# FC_v2_0_Schematic.net
KiCad netlist of a schematic drawn in Altium Designer
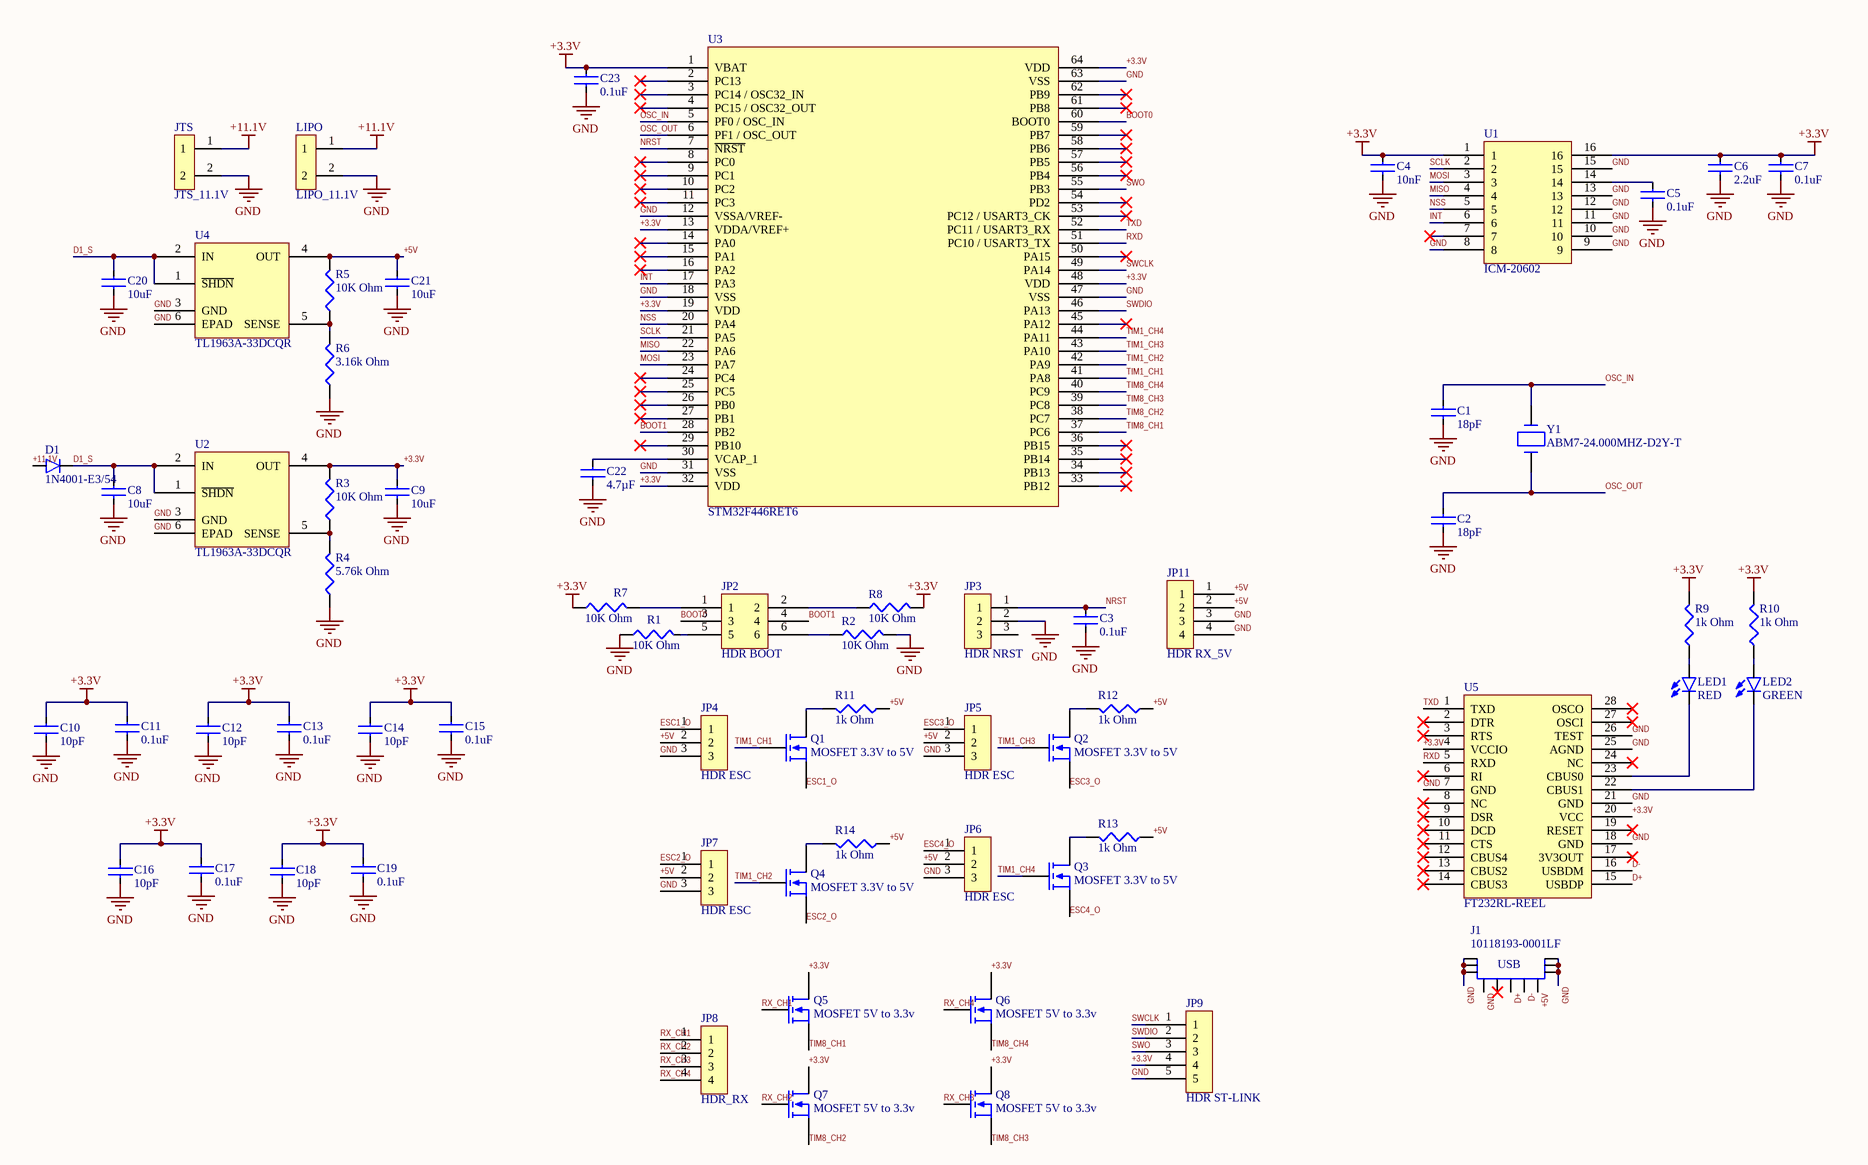
[diagram p0: FC_v2.0_Schematic.SchDoc]

(export (version "E")
  (design (tool "Eeschema 10.0.6"))
  (components
    (comp (ref "C1")
      (value "18pF")
      (footprint "C0805")
      (description "Cap Ceramic 18pF 50V C0G 5% SMD 0805 125C Paper T/R")
      (fields
        (field (name "MANUFACTURER") "Samsung")
        (field (name "MANUFACTURER PART NUMBER") "CL21C180JBANNNC")
      )
      (libsource (lib "FC_v2.0_Schlib") (part "CL21C180JBANNNC"))
    )
    (comp (ref "C2")
      (value "18pF")
      (footprint "C0805")
      (description "Cap Ceramic 18pF 50V C0G 5% SMD 0805 125C Paper T/R")
      (fields
        (field (name "MANUFACTURER") "Samsung")
        (field (name "MANUFACTURER PART NUMBER") "CL21C180JBANNNC")
      )
      (libsource (lib "FC_v2.0_Schlib") (part "CL21C180JBANNNC"))
    )
    (comp (ref "C3")
      (value "0.1uF")
      (footprint "C0805")
      (description "Cap Ceramic 0.1uF 16V X7R 10% SMD 0805 125C Paper T/R")
      (fields
        (field (name "MANUFACTURER") "Samsung")
        (field (name "MANUFACTURER PART NUMBER") "CL21B104KOANNNC")
      )
      (libsource (lib "FC_v1.0_Schlib") (part "CL21B104KOANNNC"))
    )
    (comp (ref "C4")
      (value "10nF")
      (footprint "C0805")
      (description "CAP CER 10000PF 50V X7R 0805")
      (fields
        (field (name "MANUFACTURER") "Yageo")
        (field (name "MANUFACTURER PART NUMBER") "CC0805KRX7R9BB103")
      )
      (libsource (lib "FC_v2.0_Schlib") (part "CC0805KRX7R9BB103"))
    )
    (comp (ref "C5")
      (value "0.1uF")
      (footprint "C0805")
      (description "Cap Ceramic 0.1uF 16V X7R 10% SMD 0805 125C Paper T/R")
      (fields
        (field (name "MANUFACTURER") "Samsung")
        (field (name "MANUFACTURER PART NUMBER") "CL21B104KOANNNC")
      )
      (libsource (lib "FC_v2.0_Schlib") (part "CL21B104KOANNNC"))
    )
    (comp (ref "C6")
      (value "2.2uF")
      (footprint "C0805")
      (description "CAP CER 2.2UF 16V X5R 0805")
      (fields
        (field (name "MANUFACTURER") "Taiyo Yuden")
        (field (name "MANUFACTURER PART NUMBER") "EMK212BJ225KG-T")
      )
      (libsource (lib "FC_v2.0_Schlib") (part "EMK212BJ225KG-T"))
    )
    (comp (ref "C7")
      (value "0.1uF")
      (footprint "C0805")
      (description "Cap Ceramic 0.1uF 16V X7R 10% SMD 0805 125C Paper T/R")
      (fields
        (field (name "MANUFACTURER") "Samsung")
        (field (name "MANUFACTURER PART NUMBER") "CL21B104KOANNNC")
      )
      (libsource (lib "FC_v2.0_Schlib") (part "CL21B104KOANNNC"))
    )
    (comp (ref "C8")
      (value "10uF")
      (footprint "C0805")
      (description "Cap Ceramic 10uF 16V X5R 10% SMD 0805 85C T/R")
      (fields
        (field (name "MANUFACTURER") "Samsung")
        (field (name "MANUFACTURER PART NUMBER") "CL21A106KOQNNNE")
      )
      (libsource (lib "FC_v2.0_Schlib") (part "CL21A106KOQNNNE"))
    )
    (comp (ref "C9")
      (value "10uF")
      (footprint "C0805")
      (description "Cap Ceramic 10uF 16V X5R 10% SMD 0805 85C T/R")
      (fields
        (field (name "MANUFACTURER") "Samsung")
        (field (name "MANUFACTURER PART NUMBER") "CL21A106KOQNNNE")
      )
      (libsource (lib "FC_v2.0_Schlib") (part "CL21A106KOQNNNE"))
    )
    (comp (ref "C10")
      (value "10pF")
      (footprint "C0805")
      (description "Multilayer Ceramic Capacitors MLCC - SMD/SMT 16volts 10pF C0G 20%")
      (fields
        (field (name "MANUFACTURER") "KEMET")
        (field (name "MANUFACTURER PART NUMBER") "C0805C100M4GACTU")
      )
      (libsource (lib "FC_v2.0_Schlib") (part "C0805C100M4GACTU_1"))
    )
    (comp (ref "C11")
      (value "0.1uF")
      (footprint "C0805")
      (description "Cap Ceramic 0.1uF 16V X7R 10% SMD 0805 125C Paper T/R")
      (fields
        (field (name "MANUFACTURER") "Samsung")
        (field (name "MANUFACTURER PART NUMBER") "CL21B104KOANNNC")
      )
      (libsource (lib "FC_v2.0_Schlib") (part "CL21B104KOANNNC"))
    )
    (comp (ref "C12")
      (value "10pF")
      (footprint "C0805")
      (description "Multilayer Ceramic Capacitors MLCC - SMD/SMT 16volts 10pF C0G 20%")
      (fields
        (field (name "MANUFACTURER") "KEMET")
        (field (name "MANUFACTURER PART NUMBER") "C0805C100M4GACTU")
      )
      (libsource (lib "FC_v2.0_Schlib") (part "C0805C100M4GACTU_1"))
    )
    (comp (ref "C13")
      (value "0.1uF")
      (footprint "C0805")
      (description "Cap Ceramic 0.1uF 16V X7R 10% SMD 0805 125C Paper T/R")
      (fields
        (field (name "MANUFACTURER") "Samsung")
        (field (name "MANUFACTURER PART NUMBER") "CL21B104KOANNNC")
      )
      (libsource (lib "FC_v2.0_Schlib") (part "CL21B104KOANNNC"))
    )
    (comp (ref "C14")
      (value "10pF")
      (footprint "C0805")
      (description "Multilayer Ceramic Capacitors MLCC - SMD/SMT 16volts 10pF C0G 20%")
      (fields
        (field (name "MANUFACTURER") "KEMET")
        (field (name "MANUFACTURER PART NUMBER") "C0805C100M4GACTU")
      )
      (libsource (lib "FC_v2.0_Schlib") (part "C0805C100M4GACTU_1"))
    )
    (comp (ref "C15")
      (value "0.1uF")
      (footprint "C0805")
      (description "Cap Ceramic 0.1uF 16V X7R 10% SMD 0805 125C Paper T/R")
      (fields
        (field (name "MANUFACTURER") "Samsung")
        (field (name "MANUFACTURER PART NUMBER") "CL21B104KOANNNC")
      )
      (libsource (lib "FC_v2.0_Schlib") (part "CL21B104KOANNNC"))
    )
    (comp (ref "C16")
      (value "10pF")
      (footprint "C0805")
      (description "Multilayer Ceramic Capacitors MLCC - SMD/SMT 16volts 10pF C0G 20%")
      (fields
        (field (name "MANUFACTURER") "KEMET")
        (field (name "MANUFACTURER PART NUMBER") "C0805C100M4GACTU")
      )
      (libsource (lib "FC_v2.0_Schlib") (part "C0805C100M4GACTU_1"))
    )
    (comp (ref "C17")
      (value "0.1uF")
      (footprint "C0805")
      (description "Cap Ceramic 0.1uF 16V X7R 10% SMD 0805 125C Paper T/R")
      (fields
        (field (name "MANUFACTURER") "Samsung")
        (field (name "MANUFACTURER PART NUMBER") "CL21B104KOANNNC")
      )
      (libsource (lib "FC_v2.0_Schlib") (part "CL21B104KOANNNC"))
    )
    (comp (ref "C18")
      (value "10pF")
      (footprint "C0805")
      (description "Multilayer Ceramic Capacitors MLCC - SMD/SMT 16volts 10pF C0G 20%")
      (fields
        (field (name "MANUFACTURER") "KEMET")
        (field (name "MANUFACTURER PART NUMBER") "C0805C100M4GACTU")
      )
      (libsource (lib "FC_v2.0_Schlib") (part "C0805C100M4GACTU_1"))
    )
    (comp (ref "C19")
      (value "0.1uF")
      (footprint "C0805")
      (description "Cap Ceramic 0.1uF 16V X7R 10% SMD 0805 125C Paper T/R")
      (fields
        (field (name "MANUFACTURER") "Samsung")
        (field (name "MANUFACTURER PART NUMBER") "CL21B104KOANNNC")
      )
      (libsource (lib "FC_v2.0_Schlib") (part "CL21B104KOANNNC"))
    )
    (comp (ref "C20")
      (value "10uF")
      (footprint "C0805")
      (description "Cap Ceramic 10uF 16V X5R 10% SMD 0805 85C T/R")
      (fields
        (field (name "MANUFACTURER") "Samsung")
        (field (name "MANUFACTURER PART NUMBER") "CL21A106KOQNNNE")
      )
      (libsource (lib "FC_v2.0_Schlib") (part "CL21A106KOQNNNE"))
    )
    (comp (ref "C21")
      (value "10uF")
      (footprint "C0805")
      (description "Cap Ceramic 10uF 16V X5R 10% SMD 0805 85C T/R")
      (fields
        (field (name "MANUFACTURER") "Samsung")
        (field (name "MANUFACTURER PART NUMBER") "CL21A106KOQNNNE")
      )
      (libsource (lib "FC_v2.0_Schlib") (part "CL21A106KOQNNNE"))
    )
    (comp (ref "C22")
      (value "4.7µF")
      (footprint "C0805")
      (description "Multilayer Ceramic Capacitors MLCC - SMD/SMT 4.7M pF 10% 25 Volts")
      (fields
        (field (name "MANUFACTURER") "Yageo")
        (field (name "MANUFACTURER PART NUMBER") "CC0805KKX7R8BB475")
      )
      (libsource (lib "FC_v2.0_Schlib") (part "CC0805KKX7R8BB475"))
    )
    (comp (ref "C23")
      (value "0.1uF")
      (footprint "C0805")
      (description "Cap Ceramic 0.1uF 16V X7R 10% SMD 0805 125C Paper T/R")
      (fields
        (field (name "MANUFACTURER") "Samsung")
        (field (name "MANUFACTURER PART NUMBER") "CL21B104KOANNNC")
      )
      (libsource (lib "FC_v2.0_Schlib") (part "CL21B104KOANNNC"))
    )
    (comp (ref "D1")
      (value "1N4001-E3/54")
      (footprint "DIODE")
      (description "Rectifiers Vr/50V Io/1A")
      (fields
        (field (name "MANUFACTURER") "Vishay Semiconductors")
        (field (name "MANUFACTURER PART NUMBER") "1N4001-E3/73")
      )
      (libsource (lib "FC_v1.0_Schlib") (part "1N4001-E3/73"))
    )
    (comp (ref "J1")
      (value "10118193-0001LF")
      (footprint "10118193")
      (description "USB - micro B USB 2.0 Receptacle Connector 5 Position Surface Mount, Right Angle, Horizontal")
      (fields (field (name "MANUFACTURER") "Amphenol FCI"))
      (libsource (lib "FC_v2.0_Schlib") (part "10118193-0001LF"))
    )
    (comp (ref "JP2")
      (value "HDR BOOT")
      (footprint "HDR_MALE_BOOT")
      (description "4 Positions Header, Unshrouded Connector 0.100\" (2.54mm) Through Hole Gold or Gold, GXT™")
      (fields
        (field (name "MANUFACTURER") "Amphenol FCI")
        (field (name "MANUFACTURER PART NUMBER") "68001-204HLF")
      )
      (libsource (lib "FC_v2.0_Schlib") (part "68001-204HLF_BOOT"))
    )
    (comp (ref "JP3")
      (value "HDR NRST")
      (footprint "HDR_Male_NRST")
      (description "4 Positions Header, Unshrouded Connector 0.100\" (2.54mm) Through Hole Gold or Gold, GXT™")
      (fields
        (field (name "MANUFACTURER") "Amphenol FCI")
        (field (name "MANUFACTURER PART NUMBER") "68001-204HLF")
      )
      (libsource (lib "FC_v2.0_Schlib") (part "68001-204HLF_NRST"))
    )
    (comp (ref "JP4")
      (value "HDR ESC")
      (footprint "HDR_Male_ESC")
      (description "4 Positions Header, Unshrouded Connector 0.100\" (2.54mm) Through Hole Gold or Gold, GXT™")
      (fields
        (field (name "MANUFACTURER") "Amphenol FCI")
        (field (name "MANUFACTURER PART NUMBER") "68001-204HLF")
      )
      (libsource (lib "FC_v1.0_Schlib") (part "68001-204HLF_ESC"))
    )
    (comp (ref "JP5")
      (value "HDR ESC")
      (footprint "HDR_Male_ESC")
      (description "4 Positions Header, Unshrouded Connector 0.100\" (2.54mm) Through Hole Gold or Gold, GXT™")
      (fields
        (field (name "MANUFACTURER") "Amphenol FCI")
        (field (name "MANUFACTURER PART NUMBER") "68001-204HLF")
      )
      (libsource (lib "FC_v1.0_Schlib") (part "68001-204HLF_ESC"))
    )
    (comp (ref "JP6")
      (value "HDR ESC")
      (footprint "HDR_Male_ESC")
      (description "4 Positions Header, Unshrouded Connector 0.100\" (2.54mm) Through Hole Gold or Gold, GXT™")
      (fields
        (field (name "MANUFACTURER") "Amphenol FCI")
        (field (name "MANUFACTURER PART NUMBER") "68001-204HLF")
      )
      (libsource (lib "FC_v1.0_Schlib") (part "68001-204HLF_ESC"))
    )
    (comp (ref "JP7")
      (value "HDR ESC")
      (footprint "HDR_Male_ESC")
      (description "4 Positions Header, Unshrouded Connector 0.100\" (2.54mm) Through Hole Gold or Gold, GXT™")
      (fields
        (field (name "MANUFACTURER") "Amphenol FCI")
        (field (name "MANUFACTURER PART NUMBER") "68001-204HLF")
      )
      (libsource (lib "FC_v1.0_Schlib") (part "68001-204HLF_ESC"))
    )
    (comp (ref "JP8")
      (value "HDR_RX")
      (footprint "HDR_Male_RX")
      (description "4 Positions Header, Unshrouded Connector 0.100\" (2.54mm) Through Hole Gold or Gold, GXT™")
      (fields
        (field (name "MANUFACTURER") "Amphenol FCI")
        (field (name "MANUFACTURER PART NUMBER") "68001-204HLF")
      )
      (libsource (lib "FC_v2.0_Schlib") (part "68001-204HLF_RX"))
    )
    (comp (ref "JP9")
      (value "HDR ST-LINK")
      (footprint "HDR_Male_ST-LINK")
      (description "4 Positions Header, Unshrouded Connector 0.100\" (2.54mm) Through Hole Gold or Gold, GXT™")
      (fields
        (field (name "MANUFACTURER") "Amphenol FCI")
        (field (name "MANUFACTURER PART NUMBER") "68001-204HLF")
      )
      (libsource (lib "FC_v2.0_Schlib") (part "68001-204HLF_ST-LINK"))
    )
    (comp (ref "JP11")
      (value "HDR RX_5V")
      (footprint "HDR_Male_RX_5V")
      (description "4 Positions Header, Unshrouded Connector 0.100\" (2.54mm) Through Hole Gold or Gold, GXT™")
      (fields
        (field (name "MANUFACTURER") "Amphenol FCI")
        (field (name "MANUFACTURER PART NUMBER") "68001-204HLF")
      )
      (libsource (lib "FC_v2.0_Schlib") (part "68001-204HLF_RX_5V"))
    )
    (comp (ref "JTS")
      (value "JTS_11.1V")
      (footprint "JTS_11.1V")
      (libsource (lib "FC_v2.0_Schlib") (part "JTS_11.1V"))
    )
    (comp (ref "LED1")
      (value "RED")
      (footprint "LED")
      (description "LED RED CLEAR 0805 SMD")
      (fields (field (name "MANUFACTURER") "Rohm") (field (name "MANUFACTURER PART NUMBER") "SML-M13VTT86"))
      (libsource (lib "FC_v2.0_Schlib") (part "SML-M13VTT86"))
    )
    (comp (ref "LED2")
      (value "GREEN")
      (footprint "LED")
      (description "LED GREEN CLEAR 0805 SMD")
      (fields (field (name "MANUFACTURER") "Rohm") (field (name "MANUFACTURER PART NUMBER") "SML-M13PTT86"))
      (libsource (lib "FC_v2.0_Schlib") (part "SML-M13PTT86"))
    )
    (comp (ref "LIPO")
      (value "LIPO_11.1V")
      (footprint "LIPO_11.1V")
      (libsource (lib "FC_v2.0_Schlib") (part "LIPO_11.1V"))
    )
    (comp (ref "Q1")
      (value "MOSFET 3.3V to 5V")
      (footprint "MOSFET")
      (description "MOSFET 50V N-CH Logic Level")
      (fields
        (field (name "MANUFACTURER") "Fairchild Semiconductor")
        (field (name "MANUFACTURER PART NUMBER") "BSS138W")
      )
      (libsource (lib "FC_v1.0_Schlib") (part "BSS138W"))
    )
    (comp (ref "Q2")
      (value "MOSFET 3.3V to 5V")
      (footprint "MOSFET")
      (description "MOSFET 50V N-CH Logic Level")
      (fields
        (field (name "MANUFACTURER") "Fairchild Semiconductor")
        (field (name "MANUFACTURER PART NUMBER") "BSS138W")
      )
      (libsource (lib "FC_v1.0_Schlib") (part "BSS138W"))
    )
    (comp (ref "Q3")
      (value "MOSFET 3.3V to 5V")
      (footprint "MOSFET")
      (description "MOSFET 50V N-CH Logic Level")
      (fields
        (field (name "MANUFACTURER") "Fairchild Semiconductor")
        (field (name "MANUFACTURER PART NUMBER") "BSS138W")
      )
      (libsource (lib "FC_v1.0_Schlib") (part "BSS138W"))
    )
    (comp (ref "Q4")
      (value "MOSFET 3.3V to 5V")
      (footprint "MOSFET")
      (description "MOSFET 50V N-CH Logic Level")
      (fields
        (field (name "MANUFACTURER") "Fairchild Semiconductor")
        (field (name "MANUFACTURER PART NUMBER") "BSS138W")
      )
      (libsource (lib "FC_v1.0_Schlib") (part "BSS138W"))
    )
    (comp (ref "Q5")
      (value "MOSFET 5V to 3.3v")
      (footprint "MOSFET")
      (description "MOSFET 50V N-CH Logic Level")
      (fields
        (field (name "MANUFACTURER") "Fairchild Semiconductor")
        (field (name "MANUFACTURER PART NUMBER") "BSS138W")
      )
      (libsource (lib "FC_v1.0_Schlib") (part "BSS138W_1"))
    )
    (comp (ref "Q6")
      (value "MOSFET 5V to 3.3v")
      (footprint "MOSFET")
      (description "MOSFET 50V N-CH Logic Level")
      (fields
        (field (name "MANUFACTURER") "Fairchild Semiconductor")
        (field (name "MANUFACTURER PART NUMBER") "BSS138W")
      )
      (libsource (lib "FC_v1.0_Schlib") (part "BSS138W_1"))
    )
    (comp (ref "Q7")
      (value "MOSFET 5V to 3.3v")
      (footprint "MOSFET")
      (description "MOSFET 50V N-CH Logic Level")
      (fields
        (field (name "MANUFACTURER") "Fairchild Semiconductor")
        (field (name "MANUFACTURER PART NUMBER") "BSS138W")
      )
      (libsource (lib "FC_v1.0_Schlib") (part "BSS138W_1"))
    )
    (comp (ref "Q8")
      (value "MOSFET 5V to 3.3v")
      (footprint "MOSFET")
      (description "MOSFET 50V N-CH Logic Level")
      (fields
        (field (name "MANUFACTURER") "Fairchild Semiconductor")
        (field (name "MANUFACTURER PART NUMBER") "BSS138W")
      )
      (libsource (lib "FC_v1.0_Schlib") (part "BSS138W_1"))
    )
    (comp (ref "R1")
      (value "10K Ohm")
      (footprint "R0805")
      (description "YAGEO         RC0805JR-0710KL             RES, THICK FILM, 10K, 5%, 0.125W, 0805")
      (fields
        (field (name "MANUFACTURER") "Yageo")
        (field (name "MANUFACTURER PART NUMBER") "RC0805JR-0710KL")
      )
      (libsource (lib "FC_v1.0_Schlib") (part "RC0805JR-0710KL"))
    )
    (comp (ref "R2")
      (value "10K Ohm")
      (footprint "R0805")
      (description "YAGEO         RC0805JR-0710KL             RES, THICK FILM, 10K, 5%, 0.125W, 0805")
      (fields
        (field (name "MANUFACTURER") "Yageo")
        (field (name "MANUFACTURER PART NUMBER") "RC0805JR-0710KL")
      )
      (libsource (lib "FC_v1.0_Schlib") (part "RC0805JR-0710KL"))
    )
    (comp (ref "R3")
      (value "10K Ohm")
      (footprint "R0805")
      (description "YAGEO         RC0805JR-0710KL             RES, THICK FILM, 10K, 5%, 0.125W, 0805")
      (fields
        (field (name "MANUFACTURER") "Yageo")
        (field (name "MANUFACTURER PART NUMBER") "RC0805JR-0710KL")
      )
      (libsource (lib "FC_v2.0_Schlib") (part "RC0805JR-0710KL"))
    )
    (comp (ref "R4")
      (value "5.76k Ohm")
      (footprint "R0805")
      (description "RESISTOR, THICK FILM, 5.76KOHM, 125mW, ± 1%")
      (fields
        (field (name "MANUFACTURER") "Panasonic ECG")
        (field (name "MANUFACTURER PART NUMBER") "ERJ-6ENF5761V")
      )
      (libsource (lib "FC_v2.0_Schlib") (part "ERJ-6ENF5761V"))
    )
    (comp (ref "R5")
      (value "10K Ohm")
      (footprint "R0805")
      (description "YAGEO         RC0805JR-0710KL             RES, THICK FILM, 10K, 5%, 0.125W, 0805")
      (fields
        (field (name "MANUFACTURER") "Yageo")
        (field (name "MANUFACTURER PART NUMBER") "RC0805JR-0710KL")
      )
      (libsource (lib "FC_v2.0_Schlib") (part "RC0805JR-0710KL"))
    )
    (comp (ref "R6")
      (value "3.16k Ohm")
      (footprint "R0805")
      (description "RES SMD 3.16K OHM 1% 1/8W 0805")
      (fields
        (field (name "MANUFACTURER") "Yageo")
        (field (name "MANUFACTURER PART NUMBER") "RC0805FR-073K16L")
      )
      (libsource (lib "FC_v2.0_Schlib") (part "RC0805FR-073K16L"))
    )
    (comp (ref "R7")
      (value "10K Ohm")
      (footprint "R0805")
      (description "YAGEO         RC0805JR-0710KL             RES, THICK FILM, 10K, 5%, 0.125W, 0805")
      (fields
        (field (name "MANUFACTURER") "Yageo")
        (field (name "MANUFACTURER PART NUMBER") "RC0805JR-0710KL")
      )
      (libsource (lib "FC_v2.0_Schlib") (part "RC0805JR-0710KL"))
    )
    (comp (ref "R8")
      (value "10K Ohm")
      (footprint "R0805")
      (description "YAGEO         RC0805JR-0710KL             RES, THICK FILM, 10K, 5%, 0.125W, 0805")
      (fields
        (field (name "MANUFACTURER") "Yageo")
        (field (name "MANUFACTURER PART NUMBER") "RC0805JR-0710KL")
      )
      (libsource (lib "FC_v2.0_Schlib") (part "RC0805JR-0710KL"))
    )
    (comp (ref "R9")
      (value "1k Ohm")
      (footprint "R0805")
      (description "RES SMD 560 OHM 5% 1/8W 0805")
      (fields
        (field (name "MANUFACTURER") "Yageo")
        (field (name "MANUFACTURER PART NUMBER") "RC0805JR-07560RL")
      )
      (libsource (lib "FC_v2.0_Schlib") (part "RC0805JR-07560RL"))
    )
    (comp (ref "R10")
      (value "1k Ohm")
      (footprint "R0805")
      (description "RES SMD 560 OHM 5% 1/8W 0805")
      (fields
        (field (name "MANUFACTURER") "Yageo")
        (field (name "MANUFACTURER PART NUMBER") "RC0805JR-07560RL")
      )
      (libsource (lib "FC_v2.0_Schlib") (part "RC0805JR-07560RL"))
    )
    (comp (ref "R11")
      (value "1k Ohm")
      (footprint "R0805")
      (description "RES SMD 560 OHM 5% 1/8W 0805")
      (fields
        (field (name "MANUFACTURER") "Yageo")
        (field (name "MANUFACTURER PART NUMBER") "RC0805JR-07560RL")
      )
      (libsource (lib "FC_v2.0_Schlib") (part "RC0805JR-07560RL"))
    )
    (comp (ref "R12")
      (value "1k Ohm")
      (footprint "R0805")
      (description "RES SMD 560 OHM 5% 1/8W 0805")
      (fields
        (field (name "MANUFACTURER") "Yageo")
        (field (name "MANUFACTURER PART NUMBER") "RC0805JR-07560RL")
      )
      (libsource (lib "FC_v2.0_Schlib") (part "RC0805JR-07560RL"))
    )
    (comp (ref "R13")
      (value "1k Ohm")
      (footprint "R0805")
      (description "RES SMD 560 OHM 5% 1/8W 0805")
      (fields
        (field (name "MANUFACTURER") "Yageo")
        (field (name "MANUFACTURER PART NUMBER") "RC0805JR-07560RL")
      )
      (libsource (lib "FC_v2.0_Schlib") (part "RC0805JR-07560RL"))
    )
    (comp (ref "R14")
      (value "1k Ohm")
      (footprint "R0805")
      (description "RES SMD 560 OHM 5% 1/8W 0805")
      (fields
        (field (name "MANUFACTURER") "Yageo")
        (field (name "MANUFACTURER PART NUMBER") "RC0805JR-07560RL")
      )
      (libsource (lib "FC_v2.0_Schlib") (part "RC0805JR-07560RL"))
    )
    (comp (ref "U1")
      (value "ICM-20602")
      (footprint "LGA")
      (description "WORLD'S BEST 6-AXIS INTEGRATED S")
      (fields (field (name "MANUFACTURER") "InvenSense"))
      (libsource (lib "FC_v2.0_Schlib") (part "ICM-20602"))
    )
    (comp (ref "U2")
      (value "TL1963A-33DCQR")
      (footprint "DCQ")
      (description "IC REG LDO 3.3V 1.5A SOT223-6")
      (fields (field (name "MANUFACTURER") "Texas Instruments"))
      (libsource (lib "FC_v2.0_Schlib") (part "TL1963A-33DCQR"))
    )
    (comp (ref "U3")
      (value "STM32F446RET6")
      (footprint "STM32F446xC")
      (fields (field (name "MANUFACTURER") "STMicroelectronics"))
      (libsource (lib "FC_v2.0_Schlib") (part "STM32F446RET6"))
    )
    (comp (ref "U4")
      (value "TL1963A-33DCQR")
      (footprint "DCQ")
      (description "IC REG LDO 3.3V 1.5A SOT223-6")
      (fields (field (name "MANUFACTURER") "Texas Instruments"))
      (libsource (lib "FC_v2.0_Schlib") (part "TL1963A-33DCQR"))
    )
    (comp (ref "U5")
      (value "FT232RL-REEL")
      (footprint "SSOP_28")
      (description "IC USB FS SERIAL UART 28-SSOP")
      (fields (field (name "MANUFACTURER") "FTDI"))
      (libsource (lib "FC_v2.0_Schlib") (part "FT232RL-REEL"))
    )
    (comp (ref "Y1")
      (value "ABM7-24.000MHZ-D2Y-T")
      (footprint "AMB7_v1_0_BIG")
      (description "ABRACON         ABM7-24.000MHZ-D2Y-T             CRYSTAL, 24MHZ, 18PF, 6 X 3.5MM")
      (fields (field (name "MANUFACTURER") "Abracon"))
      (libsource (lib "FC_v2.0_Schlib") (part "ABM7-24.000MHZ-D2Y-T"))
    )
  )
  (nets
    (net (code "1") (name "+3.3V") (class "Default")
      (node (ref "C10") (pin "1") (pinfunction "1_1") (pintype "passive"))
      (node (ref "C11") (pin "1") (pinfunction "1_1") (pintype "passive"))
      (node (ref "C12") (pin "1") (pinfunction "1_1") (pintype "passive"))
      (node (ref "C13") (pin "1") (pinfunction "1_1") (pintype "passive"))
      (node (ref "C14") (pin "1") (pinfunction "1_1") (pintype "passive"))
      (node (ref "C15") (pin "1") (pinfunction "1_1") (pintype "passive"))
      (node (ref "C16") (pin "1") (pinfunction "1_1") (pintype "passive"))
      (node (ref "C17") (pin "1") (pinfunction "1_1") (pintype "passive"))
      (node (ref "C18") (pin "1") (pinfunction "1_1") (pintype "passive"))
      (node (ref "C19") (pin "1") (pinfunction "1_1") (pintype "passive"))
      (node (ref "C23") (pin "1") (pinfunction "1_1") (pintype "passive"))
      (node (ref "C4") (pin "1") (pinfunction "1_1") (pintype "passive"))
      (node (ref "C6") (pin "1") (pinfunction "1_1") (pintype "passive"))
      (node (ref "C7") (pin "1") (pinfunction "1_1") (pintype "passive"))
      (node (ref "C9") (pin "1") (pinfunction "1_1") (pintype "passive"))
      (node (ref "JP9") (pin "4") (pinfunction "4_4") (pintype "passive"))
      (node (ref "Q5") (pin "3") (pinfunction "3_3") (pintype "passive"))
      (node (ref "Q6") (pin "3") (pinfunction "3_3") (pintype "passive"))
      (node (ref "Q7") (pin "3") (pinfunction "3_3") (pintype "passive"))
      (node (ref "Q8") (pin "3") (pinfunction "3_3") (pintype "passive"))
      (node (ref "R10") (pin "2") (pinfunction "2_2") (pintype "passive"))
      (node (ref "R3") (pin "2") (pinfunction "2_2") (pintype "passive"))
      (node (ref "R7") (pin "1") (pinfunction "1_1") (pintype "passive"))
      (node (ref "R8") (pin "2") (pinfunction "2_2") (pintype "passive"))
      (node (ref "R9") (pin "2") (pinfunction "2_2") (pintype "passive"))
      (node (ref "U1") (pin "1") (pinfunction "1_1") (pintype "passive"))
      (node (ref "U1") (pin "16") (pinfunction "16_16") (pintype "passive"))
      (node (ref "U2") (pin "4") (pinfunction "OUT_4") (pintype "passive"))
      (node (ref "U3") (pin "1") (pinfunction "VBAT_1") (pintype "passive"))
      (node (ref "U3") (pin "13") (pinfunction "VDDA/VREF+_13") (pintype "passive"))
      (node (ref "U3") (pin "19") (pinfunction "VDD_19") (pintype "passive"))
      (node (ref "U3") (pin "32") (pinfunction "VDD_32") (pintype "passive"))
      (node (ref "U3") (pin "48") (pinfunction "VDD_48") (pintype "passive"))
      (node (ref "U3") (pin "64") (pinfunction "VDD_64") (pintype "passive"))
      (node (ref "U5") (pin "20") (pinfunction "VCC_20") (pintype "passive"))
      (node (ref "U5") (pin "4") (pinfunction "VCCIO_4") (pintype "passive"))
    )
    (net (code "2") (name "+11.1V") (class "Default")
      (node (ref "D1") (pin "1") (pinfunction "1_1") (pintype "passive"))
      (node (ref "JTS") (pin "1") (pinfunction "1_1") (pintype "passive"))
      (node (ref "LIPO") (pin "1") (pinfunction "1_1") (pintype "passive"))
    )
    (net (code "3") (name "/+5V") (class "Default")
      (node (ref "C21") (pin "1") (pinfunction "1_1") (pintype "passive"))
      (node (ref "J1") (pin "1") (pinfunction "1_1") (pintype "passive"))
      (node (ref "JP11") (pin "1") (pinfunction "1_1") (pintype "passive"))
      (node (ref "JP11") (pin "2") (pinfunction "2_2") (pintype "passive"))
      (node (ref "JP4") (pin "2") (pinfunction "2_2") (pintype "passive"))
      (node (ref "JP5") (pin "2") (pinfunction "2_2") (pintype "passive"))
      (node (ref "JP6") (pin "2") (pinfunction "2_2") (pintype "passive"))
      (node (ref "JP7") (pin "2") (pinfunction "2_2") (pintype "passive"))
      (node (ref "R11") (pin "1") (pinfunction "1_1") (pintype "passive"))
      (node (ref "R12") (pin "1") (pinfunction "1_1") (pintype "passive"))
      (node (ref "R13") (pin "1") (pinfunction "1_1") (pintype "passive"))
      (node (ref "R14") (pin "1") (pinfunction "1_1") (pintype "passive"))
      (node (ref "R5") (pin "2") (pinfunction "2_2") (pintype "passive"))
      (node (ref "U4") (pin "4") (pinfunction "OUT_4") (pintype "passive"))
    )
    (net (code "4") (name "/BOOT0") (class "Default")
      (node (ref "JP2") (pin "3") (pinfunction "3_3") (pintype "passive"))
      (node (ref "U3") (pin "60") (pinfunction "BOOT0_60") (pintype "passive"))
    )
    (net (code "5") (name "/BOOT1") (class "Default")
      (node (ref "JP2") (pin "4") (pinfunction "4_4") (pintype "passive"))
      (node (ref "U3") (pin "28") (pinfunction "PB2_28") (pintype "passive"))
    )
    (net (code "6") (name "/D+") (class "Default")
      (node (ref "J1") (pin "3") (pinfunction "3_3") (pintype "passive"))
      (node (ref "U5") (pin "15") (pinfunction "USBDP_15") (pintype "passive"))
    )
    (net (code "7") (name "/D-") (class "Default")
      (node (ref "J1") (pin "2") (pinfunction "2_2") (pintype "passive"))
      (node (ref "U5") (pin "16") (pinfunction "USBDM_16") (pintype "passive"))
    )
    (net (code "8") (name "/D1_S") (class "Default")
      (node (ref "C20") (pin "1") (pinfunction "1_1") (pintype "passive"))
      (node (ref "C8") (pin "1") (pinfunction "1_1") (pintype "passive"))
      (node (ref "D1") (pin "2") (pinfunction "2_2") (pintype "passive"))
      (node (ref "U2") (pin "1") (pinfunction "~{SHDN}_1") (pintype "passive"))
      (node (ref "U2") (pin "2") (pinfunction "IN_2") (pintype "passive"))
      (node (ref "U4") (pin "1") (pinfunction "~{SHDN}_1") (pintype "passive"))
      (node (ref "U4") (pin "2") (pinfunction "IN_2") (pintype "passive"))
    )
    (net (code "9") (name "/ESC1_O") (class "Default")
      (node (ref "JP4") (pin "1") (pinfunction "1_1") (pintype "passive"))
      (node (ref "Q1") (pin "2") (pinfunction "2_2") (pintype "passive"))
    )
    (net (code "10") (name "/ESC2_O") (class "Default")
      (node (ref "JP7") (pin "1") (pinfunction "1_1") (pintype "passive"))
      (node (ref "Q4") (pin "2") (pinfunction "2_2") (pintype "passive"))
    )
    (net (code "11") (name "/ESC3_O") (class "Default")
      (node (ref "JP5") (pin "1") (pinfunction "1_1") (pintype "passive"))
      (node (ref "Q2") (pin "2") (pinfunction "2_2") (pintype "passive"))
    )
    (net (code "12") (name "/ESC4_O") (class "Default")
      (node (ref "JP6") (pin "1") (pinfunction "1_1") (pintype "passive"))
      (node (ref "Q3") (pin "2") (pinfunction "2_2") (pintype "passive"))
    )
    (net (code "13") (name "/INT") (class "Default")
      (node (ref "U1") (pin "6") (pinfunction "6_6") (pintype "passive"))
      (node (ref "U3") (pin "17") (pinfunction "PA3_17") (pintype "passive"))
    )
    (net (code "14") (name "/MISO") (class "Default")
      (node (ref "U1") (pin "4") (pinfunction "4_4") (pintype "passive"))
      (node (ref "U3") (pin "22") (pinfunction "PA6_22") (pintype "passive"))
    )
    (net (code "15") (name "/MOSI") (class "Default")
      (node (ref "U1") (pin "3") (pinfunction "3_3") (pintype "passive"))
      (node (ref "U3") (pin "23") (pinfunction "PA7_23") (pintype "passive"))
    )
    (net (code "16") (name "/NRST") (class "Default")
      (node (ref "C3") (pin "1") (pinfunction "1_1") (pintype "passive"))
      (node (ref "JP3") (pin "1") (pinfunction "1_1") (pintype "passive"))
      (node (ref "U3") (pin "7") (pinfunction "~{NRST}_7") (pintype "passive"))
    )
    (net (code "17") (name "/NSS") (class "Default")
      (node (ref "U1") (pin "5") (pinfunction "5_5") (pintype "passive"))
      (node (ref "U3") (pin "20") (pinfunction "PA4_20") (pintype "passive"))
    )
    (net (code "18") (name "/OSC_IN") (class "Default")
      (node (ref "C1") (pin "1") (pinfunction "1_1") (pintype "passive"))
      (node (ref "U3") (pin "5") (pinfunction "PF0_/_OSC_IN_5") (pintype "passive"))
      (node (ref "Y1") (pin "2") (pinfunction "2_2") (pintype "passive"))
    )
    (net (code "19") (name "/OSC_OUT") (class "Default")
      (node (ref "C2") (pin "1") (pinfunction "1_1") (pintype "passive"))
      (node (ref "U3") (pin "6") (pinfunction "PF1_/_OSC_OUT_6") (pintype "passive"))
      (node (ref "Y1") (pin "1") (pinfunction "1_1") (pintype "passive"))
    )
    (net (code "20") (name "/RXD") (class "Default")
      (node (ref "U3") (pin "51") (pinfunction "PC10_/_USART3_TX_51") (pintype "passive"))
      (node (ref "U5") (pin "5") (pinfunction "RXD_5") (pintype "passive"))
    )
    (net (code "21") (name "/RX_CH1") (class "Default")
      (node (ref "JP8") (pin "1") (pinfunction "1_1") (pintype "passive"))
      (node (ref "Q5") (pin "1") (pinfunction "1_1") (pintype "passive"))
    )
    (net (code "22") (name "/RX_CH2") (class "Default")
      (node (ref "JP8") (pin "2") (pinfunction "2_2") (pintype "passive"))
      (node (ref "Q7") (pin "1") (pinfunction "1_1") (pintype "passive"))
    )
    (net (code "23") (name "/RX_CH3") (class "Default")
      (node (ref "JP8") (pin "3") (pinfunction "3_3") (pintype "passive"))
      (node (ref "Q8") (pin "1") (pinfunction "1_1") (pintype "passive"))
    )
    (net (code "24") (name "/RX_CH4") (class "Default")
      (node (ref "JP8") (pin "4") (pinfunction "4_4") (pintype "passive"))
      (node (ref "Q6") (pin "1") (pinfunction "1_1") (pintype "passive"))
    )
    (net (code "25") (name "/SCLK") (class "Default")
      (node (ref "U1") (pin "2") (pinfunction "2_2") (pintype "passive"))
      (node (ref "U3") (pin "21") (pinfunction "PA5_21") (pintype "passive"))
    )
    (net (code "26") (name "/SWCLK") (class "Default")
      (node (ref "JP9") (pin "1") (pinfunction "1_1") (pintype "passive"))
      (node (ref "U3") (pin "49") (pinfunction "PA14_49") (pintype "passive"))
    )
    (net (code "27") (name "/SWDIO") (class "Default")
      (node (ref "JP9") (pin "2") (pinfunction "2_2") (pintype "passive"))
      (node (ref "U3") (pin "46") (pinfunction "PA13_46") (pintype "passive"))
    )
    (net (code "28") (name "/SWO") (class "Default")
      (node (ref "JP9") (pin "3") (pinfunction "3_3") (pintype "passive"))
      (node (ref "U3") (pin "55") (pinfunction "PB3_55") (pintype "passive"))
    )
    (net (code "29") (name "/TIM1_CH1") (class "Default")
      (node (ref "Q1") (pin "1") (pinfunction "1_1") (pintype "passive"))
      (node (ref "U3") (pin "41") (pinfunction "PA8_41") (pintype "passive"))
    )
    (net (code "30") (name "/TIM1_CH2") (class "Default")
      (node (ref "Q4") (pin "1") (pinfunction "1_1") (pintype "passive"))
      (node (ref "U3") (pin "42") (pinfunction "PA9_42") (pintype "passive"))
    )
    (net (code "31") (name "/TIM1_CH3") (class "Default")
      (node (ref "Q2") (pin "1") (pinfunction "1_1") (pintype "passive"))
      (node (ref "U3") (pin "43") (pinfunction "PA10_43") (pintype "passive"))
    )
    (net (code "32") (name "/TIM1_CH4") (class "Default")
      (node (ref "Q3") (pin "1") (pinfunction "1_1") (pintype "passive"))
      (node (ref "U3") (pin "44") (pinfunction "PA11_44") (pintype "passive"))
    )
    (net (code "33") (name "/TIM8_CH1") (class "Default")
      (node (ref "Q5") (pin "2") (pinfunction "2_2") (pintype "passive"))
      (node (ref "U3") (pin "37") (pinfunction "PC6_37") (pintype "passive"))
    )
    (net (code "34") (name "/TIM8_CH2") (class "Default")
      (node (ref "Q7") (pin "2") (pinfunction "2_2") (pintype "passive"))
      (node (ref "U3") (pin "38") (pinfunction "PC7_38") (pintype "passive"))
    )
    (net (code "35") (name "/TIM8_CH3") (class "Default")
      (node (ref "Q8") (pin "2") (pinfunction "2_2") (pintype "passive"))
      (node (ref "U3") (pin "39") (pinfunction "PC8_39") (pintype "passive"))
    )
    (net (code "36") (name "/TIM8_CH4") (class "Default")
      (node (ref "Q6") (pin "2") (pinfunction "2_2") (pintype "passive"))
      (node (ref "U3") (pin "40") (pinfunction "PC9_40") (pintype "passive"))
    )
    (net (code "37") (name "/TXD") (class "Default")
      (node (ref "U3") (pin "52") (pinfunction "PC11_/_USART3_RX_52") (pintype "passive"))
      (node (ref "U5") (pin "1") (pinfunction "TXD_1") (pintype "passive"))
    )
    (net (code "38") (name "GND") (class "Default")
      (node (ref "C1") (pin "2") (pinfunction "2_2") (pintype "passive"))
      (node (ref "C10") (pin "2") (pinfunction "2_2") (pintype "passive"))
      (node (ref "C11") (pin "2") (pinfunction "2_2") (pintype "passive"))
      (node (ref "C12") (pin "2") (pinfunction "2_2") (pintype "passive"))
      (node (ref "C13") (pin "2") (pinfunction "2_2") (pintype "passive"))
      (node (ref "C14") (pin "2") (pinfunction "2_2") (pintype "passive"))
      (node (ref "C15") (pin "2") (pinfunction "2_2") (pintype "passive"))
      (node (ref "C16") (pin "2") (pinfunction "2_2") (pintype "passive"))
      (node (ref "C17") (pin "2") (pinfunction "2_2") (pintype "passive"))
      (node (ref "C18") (pin "2") (pinfunction "2_2") (pintype "passive"))
      (node (ref "C19") (pin "2") (pinfunction "2_2") (pintype "passive"))
      (node (ref "C2") (pin "2") (pinfunction "2_2") (pintype "passive"))
      (node (ref "C20") (pin "2") (pinfunction "2_2") (pintype "passive"))
      (node (ref "C21") (pin "2") (pinfunction "2_2") (pintype "passive"))
      (node (ref "C22") (pin "2") (pinfunction "2_2") (pintype "passive"))
      (node (ref "C23") (pin "2") (pinfunction "2_2") (pintype "passive"))
      (node (ref "C3") (pin "2") (pinfunction "2_2") (pintype "passive"))
      (node (ref "C4") (pin "2") (pinfunction "2_2") (pintype "passive"))
      (node (ref "C5") (pin "2") (pinfunction "2_2") (pintype "passive"))
      (node (ref "C6") (pin "2") (pinfunction "2_2") (pintype "passive"))
      (node (ref "C7") (pin "2") (pinfunction "2_2") (pintype "passive"))
      (node (ref "C8") (pin "2") (pinfunction "2_2") (pintype "passive"))
      (node (ref "C9") (pin "2") (pinfunction "2_2") (pintype "passive"))
      (node (ref "J1") (pin "10") (pinfunction "10_10") (pintype "passive"))
      (node (ref "J1") (pin "11") (pinfunction "11_11") (pintype "passive"))
      (node (ref "J1") (pin "5") (pinfunction "5_5") (pintype "passive"))
      (node (ref "J1") (pin "6") (pinfunction "6_6") (pintype "passive"))
      (node (ref "J1") (pin "7") (pinfunction "7_7") (pintype "passive"))
      (node (ref "J1") (pin "8") (pinfunction "8_8") (pintype "passive"))
      (node (ref "J1") (pin "9") (pinfunction "9_9") (pintype "passive"))
      (node (ref "JP11") (pin "3") (pinfunction "3_3") (pintype "passive"))
      (node (ref "JP11") (pin "4") (pinfunction "4_4") (pintype "passive"))
      (node (ref "JP3") (pin "2") (pinfunction "2_2") (pintype "passive"))
      (node (ref "JP4") (pin "3") (pinfunction "3_3") (pintype "passive"))
      (node (ref "JP5") (pin "3") (pinfunction "3_3") (pintype "passive"))
      (node (ref "JP6") (pin "3") (pinfunction "3_3") (pintype "passive"))
      (node (ref "JP7") (pin "3") (pinfunction "3_3") (pintype "passive"))
      (node (ref "JP9") (pin "5") (pinfunction "5_5") (pintype "passive"))
      (node (ref "JTS") (pin "2") (pinfunction "2_2") (pintype "passive"))
      (node (ref "LIPO") (pin "2") (pinfunction "2_2") (pintype "passive"))
      (node (ref "R1") (pin "1") (pinfunction "1_1") (pintype "passive"))
      (node (ref "R2") (pin "1") (pinfunction "1_1") (pintype "passive"))
      (node (ref "R4") (pin "1") (pinfunction "1_1") (pintype "passive"))
      (node (ref "R6") (pin "1") (pinfunction "1_1") (pintype "passive"))
      (node (ref "U1") (pin "10") (pinfunction "10_10") (pintype "passive"))
      (node (ref "U1") (pin "11") (pinfunction "11_11") (pintype "passive"))
      (node (ref "U1") (pin "12") (pinfunction "12_12") (pintype "passive"))
      (node (ref "U1") (pin "13") (pinfunction "13_13") (pintype "passive"))
      (node (ref "U1") (pin "15") (pinfunction "15_15") (pintype "passive"))
      (node (ref "U1") (pin "8") (pinfunction "8_8") (pintype "passive"))
      (node (ref "U1") (pin "9") (pinfunction "9_9") (pintype "passive"))
      (node (ref "U2") (pin "3") (pinfunction "GND_3") (pintype "passive"))
      (node (ref "U2") (pin "6") (pinfunction "EPAD_6") (pintype "passive"))
      (node (ref "U3") (pin "12") (pinfunction "VSSA/VREF-_12") (pintype "passive"))
      (node (ref "U3") (pin "18") (pinfunction "VSS_18") (pintype "passive"))
      (node (ref "U3") (pin "31") (pinfunction "VSS_31") (pintype "passive"))
      (node (ref "U3") (pin "47") (pinfunction "VSS_47") (pintype "passive"))
      (node (ref "U3") (pin "63") (pinfunction "VSS_63") (pintype "passive"))
      (node (ref "U4") (pin "3") (pinfunction "GND_3") (pintype "passive"))
      (node (ref "U4") (pin "6") (pinfunction "EPAD_6") (pintype "passive"))
      (node (ref "U5") (pin "18") (pinfunction "GND_18") (pintype "passive"))
      (node (ref "U5") (pin "21") (pinfunction "GND_21") (pintype "passive"))
      (node (ref "U5") (pin "25") (pinfunction "AGND_25") (pintype "passive"))
      (node (ref "U5") (pin "26") (pinfunction "TEST_26") (pintype "passive"))
      (node (ref "U5") (pin "7") (pinfunction "GND_7") (pintype "passive"))
    )
    (net (code "39") (name "Net-(C5-Pad1)") (class "Default")
      (node (ref "C5") (pin "1") (pinfunction "1_1") (pintype "passive"))
      (node (ref "U1") (pin "14") (pinfunction "14_14") (pintype "passive"))
    )
    (net (code "40") (name "Net-(JP2-Pad1)") (class "Default")
      (node (ref "JP2") (pin "1") (pinfunction "1_1") (pintype "passive"))
      (node (ref "R7") (pin "2") (pinfunction "2_2") (pintype "passive"))
    )
    (net (code "41") (name "Net-(JP2-Pad2)") (class "Default")
      (node (ref "JP2") (pin "2") (pinfunction "2_2") (pintype "passive"))
      (node (ref "R8") (pin "1") (pinfunction "1_1") (pintype "passive"))
    )
    (net (code "42") (name "Net-(JP2-Pad5)") (class "Default")
      (node (ref "JP2") (pin "5") (pinfunction "5_5") (pintype "passive"))
      (node (ref "R1") (pin "2") (pinfunction "2_2") (pintype "passive"))
    )
    (net (code "43") (name "Net-(JP2-Pad6)") (class "Default")
      (node (ref "JP2") (pin "6") (pinfunction "6_6") (pintype "passive"))
      (node (ref "R2") (pin "2") (pinfunction "2_2") (pintype "passive"))
    )
    (net (code "44") (name "Net-(LED1-Pad1)") (class "Default")
      (node (ref "LED1") (pin "1") (pinfunction "1_1") (pintype "passive"))
      (node (ref "R9") (pin "1") (pinfunction "1_1") (pintype "passive"))
    )
    (net (code "45") (name "Net-(LED2-Pad1)") (class "Default")
      (node (ref "LED2") (pin "1") (pinfunction "1_1") (pintype "passive"))
      (node (ref "R10") (pin "1") (pinfunction "1_1") (pintype "passive"))
    )
    (net (code "46") (name "Net-(Q1-Pad3)") (class "Default")
      (node (ref "Q1") (pin "3") (pinfunction "3_3") (pintype "passive"))
      (node (ref "R11") (pin "2") (pinfunction "2_2") (pintype "passive"))
    )
    (net (code "47") (name "Net-(Q2-Pad3)") (class "Default")
      (node (ref "Q2") (pin "3") (pinfunction "3_3") (pintype "passive"))
      (node (ref "R12") (pin "2") (pinfunction "2_2") (pintype "passive"))
    )
    (net (code "48") (name "Net-(Q3-Pad3)") (class "Default")
      (node (ref "Q3") (pin "3") (pinfunction "3_3") (pintype "passive"))
      (node (ref "R13") (pin "2") (pinfunction "2_2") (pintype "passive"))
    )
    (net (code "49") (name "Net-(Q4-Pad3)") (class "Default")
      (node (ref "Q4") (pin "3") (pinfunction "3_3") (pintype "passive"))
      (node (ref "R14") (pin "2") (pinfunction "2_2") (pintype "passive"))
    )
    (net (code "50") (name "Net-(U2-SENSE)") (class "Default")
      (node (ref "R3") (pin "1") (pinfunction "1_1") (pintype "passive"))
      (node (ref "R4") (pin "2") (pinfunction "2_2") (pintype "passive"))
      (node (ref "U2") (pin "5") (pinfunction "SENSE_5") (pintype "passive"))
    )
    (net (code "51") (name "Net-(U3-VCAP_1)") (class "Default")
      (node (ref "C22") (pin "1") (pinfunction "1_1") (pintype "passive"))
      (node (ref "U3") (pin "30") (pinfunction "VCAP_1_30") (pintype "passive"))
    )
    (net (code "52") (name "Net-(U4-SENSE)") (class "Default")
      (node (ref "R5") (pin "1") (pinfunction "1_1") (pintype "passive"))
      (node (ref "R6") (pin "2") (pinfunction "2_2") (pintype "passive"))
      (node (ref "U4") (pin "5") (pinfunction "SENSE_5") (pintype "passive"))
    )
    (net (code "53") (name "Net-(U5-CBUS0)") (class "Default")
      (node (ref "LED1") (pin "2") (pinfunction "2_2") (pintype "passive"))
      (node (ref "U5") (pin "23") (pinfunction "CBUS0_23") (pintype "passive"))
    )
    (net (code "54") (name "Net-(U5-CBUS1)") (class "Default")
      (node (ref "LED2") (pin "2") (pinfunction "2_2") (pintype "passive"))
      (node (ref "U5") (pin "22") (pinfunction "CBUS1_22") (pintype "passive"))
    )
    (net (code "55") (name "unconnected-(J1-Pad4)") (class "Default")
      (node (ref "J1") (pin "4") (pinfunction "4_4") (pintype "passive+no_connect"))
    )
    (net (code "56") (name "unconnected-(JP3-Pad3)") (class "Default")
      (node (ref "JP3") (pin "3") (pinfunction "3_3") (pintype "passive"))
    )
    (net (code "57") (name "unconnected-(U1-Pad7)") (class "Default")
      (node (ref "U1") (pin "7") (pinfunction "7_7") (pintype "passive+no_connect"))
    )
    (net (code "58") (name "unconnected-(U3-PA0-Pad14)") (class "Default")
      (node (ref "U3") (pin "14") (pinfunction "PA0_14") (pintype "passive+no_connect"))
    )
    (net (code "59") (name "unconnected-(U3-PA1-Pad15)") (class "Default")
      (node (ref "U3") (pin "15") (pinfunction "PA1_15") (pintype "passive+no_connect"))
    )
    (net (code "60") (name "unconnected-(U3-PA2-Pad16)") (class "Default")
      (node (ref "U3") (pin "16") (pinfunction "PA2_16") (pintype "passive+no_connect"))
    )
    (net (code "61") (name "unconnected-(U3-PA12-Pad45)") (class "Default")
      (node (ref "U3") (pin "45") (pinfunction "PA12_45") (pintype "passive+no_connect"))
    )
    (net (code "62") (name "unconnected-(U3-PA15-Pad50)") (class "Default")
      (node (ref "U3") (pin "50") (pinfunction "PA15_50") (pintype "passive+no_connect"))
    )
    (net (code "63") (name "unconnected-(U3-PB0-Pad26)") (class "Default")
      (node (ref "U3") (pin "26") (pinfunction "PB0_26") (pintype "passive+no_connect"))
    )
    (net (code "64") (name "unconnected-(U3-PB1-Pad27)") (class "Default")
      (node (ref "U3") (pin "27") (pinfunction "PB1_27") (pintype "passive+no_connect"))
    )
    (net (code "65") (name "unconnected-(U3-PB4-Pad56)") (class "Default")
      (node (ref "U3") (pin "56") (pinfunction "PB4_56") (pintype "passive+no_connect"))
    )
    (net (code "66") (name "unconnected-(U3-PB5-Pad57)") (class "Default")
      (node (ref "U3") (pin "57") (pinfunction "PB5_57") (pintype "passive+no_connect"))
    )
    (net (code "67") (name "unconnected-(U3-PB6-Pad58)") (class "Default")
      (node (ref "U3") (pin "58") (pinfunction "PB6_58") (pintype "passive+no_connect"))
    )
    (net (code "68") (name "unconnected-(U3-PB7-Pad59)") (class "Default")
      (node (ref "U3") (pin "59") (pinfunction "PB7_59") (pintype "passive+no_connect"))
    )
    (net (code "69") (name "unconnected-(U3-PB8-Pad61)") (class "Default")
      (node (ref "U3") (pin "61") (pinfunction "PB8_61") (pintype "passive+no_connect"))
    )
    (net (code "70") (name "unconnected-(U3-PB9-Pad62)") (class "Default")
      (node (ref "U3") (pin "62") (pinfunction "PB9_62") (pintype "passive+no_connect"))
    )
    (net (code "71") (name "unconnected-(U3-PB10-Pad29)") (class "Default")
      (node (ref "U3") (pin "29") (pinfunction "PB10_29") (pintype "passive+no_connect"))
    )
    (net (code "72") (name "unconnected-(U3-PB12-Pad33)") (class "Default")
      (node (ref "U3") (pin "33") (pinfunction "PB12_33") (pintype "passive+no_connect"))
    )
    (net (code "73") (name "unconnected-(U3-PB13-Pad34)") (class "Default")
      (node (ref "U3") (pin "34") (pinfunction "PB13_34") (pintype "passive+no_connect"))
    )
    (net (code "74") (name "unconnected-(U3-PB14-Pad35)") (class "Default")
      (node (ref "U3") (pin "35") (pinfunction "PB14_35") (pintype "passive+no_connect"))
    )
    (net (code "75") (name "unconnected-(U3-PB15-Pad36)") (class "Default")
      (node (ref "U3") (pin "36") (pinfunction "PB15_36") (pintype "passive+no_connect"))
    )
    (net (code "76") (name "unconnected-(U3-PC0-Pad8)") (class "Default")
      (node (ref "U3") (pin "8") (pinfunction "PC0_8") (pintype "passive+no_connect"))
    )
    (net (code "77") (name "unconnected-(U3-PC1-Pad9)") (class "Default")
      (node (ref "U3") (pin "9") (pinfunction "PC1_9") (pintype "passive+no_connect"))
    )
    (net (code "78") (name "unconnected-(U3-PC2-Pad10)") (class "Default")
      (node (ref "U3") (pin "10") (pinfunction "PC2_10") (pintype "passive+no_connect"))
    )
    (net (code "79") (name "unconnected-(U3-PC3-Pad11)") (class "Default")
      (node (ref "U3") (pin "11") (pinfunction "PC3_11") (pintype "passive+no_connect"))
    )
    (net (code "80") (name "unconnected-(U3-PC4-Pad24)") (class "Default")
      (node (ref "U3") (pin "24") (pinfunction "PC4_24") (pintype "passive+no_connect"))
    )
    (net (code "81") (name "unconnected-(U3-PC5-Pad25)") (class "Default")
      (node (ref "U3") (pin "25") (pinfunction "PC5_25") (pintype "passive+no_connect"))
    )
    (net (code "82") (name "unconnected-(U3-PC12_{slash}_USART3_CK-Pad53)") (class "Default")
      (node (ref "U3") (pin "53") (pinfunction "PC12_/_USART3_CK_53") (pintype "passive+no_connect"))
    )
    (net (code "83") (name "unconnected-(U3-PC13-Pad2)") (class "Default")
      (node (ref "U3") (pin "2") (pinfunction "PC13_2") (pintype "passive+no_connect"))
    )
    (net (code "84") (name "unconnected-(U3-PC14_{slash}_OSC32_IN-Pad3)") (class "Default")
      (node (ref "U3") (pin "3") (pinfunction "PC14_/_OSC32_IN_3") (pintype "passive+no_connect"))
    )
    (net (code "85") (name "unconnected-(U3-PC15_{slash}_OSC32_OUT-Pad4)") (class "Default")
      (node (ref "U3") (pin "4") (pinfunction "PC15_/_OSC32_OUT_4") (pintype "passive+no_connect"))
    )
    (net (code "86") (name "unconnected-(U3-PD2-Pad54)") (class "Default")
      (node (ref "U3") (pin "54") (pinfunction "PD2_54") (pintype "passive+no_connect"))
    )
    (net (code "87") (name "unconnected-(U5-3V3OUT-Pad17)") (class "Default")
      (node (ref "U5") (pin "17") (pinfunction "3V3OUT_17") (pintype "passive+no_connect"))
    )
    (net (code "88") (name "unconnected-(U5-CBUS2-Pad13)") (class "Default")
      (node (ref "U5") (pin "13") (pinfunction "CBUS2_13") (pintype "passive+no_connect"))
    )
    (net (code "89") (name "unconnected-(U5-CBUS3-Pad14)") (class "Default")
      (node (ref "U5") (pin "14") (pinfunction "CBUS3_14") (pintype "passive+no_connect"))
    )
    (net (code "90") (name "unconnected-(U5-CBUS4-Pad12)") (class "Default")
      (node (ref "U5") (pin "12") (pinfunction "CBUS4_12") (pintype "passive+no_connect"))
    )
    (net (code "91") (name "unconnected-(U5-CTS-Pad11)") (class "Default")
      (node (ref "U5") (pin "11") (pinfunction "CTS_11") (pintype "passive+no_connect"))
    )
    (net (code "92") (name "unconnected-(U5-DCD-Pad10)") (class "Default")
      (node (ref "U5") (pin "10") (pinfunction "DCD_10") (pintype "passive+no_connect"))
    )
    (net (code "93") (name "unconnected-(U5-DSR-Pad9)") (class "Default")
      (node (ref "U5") (pin "9") (pinfunction "DSR_9") (pintype "passive+no_connect"))
    )
    (net (code "94") (name "unconnected-(U5-DTR-Pad2)") (class "Default")
      (node (ref "U5") (pin "2") (pinfunction "DTR_2") (pintype "passive+no_connect"))
    )
    (net (code "95") (name "unconnected-(U5-NC-Pad8)") (class "Default")
      (node (ref "U5") (pin "8") (pinfunction "NC_8") (pintype "passive+no_connect"))
    )
    (net (code "96") (name "unconnected-(U5-NC-Pad24)") (class "Default")
      (node (ref "U5") (pin "24") (pinfunction "NC_24") (pintype "passive+no_connect"))
    )
    (net (code "97") (name "unconnected-(U5-OSCI-Pad27)") (class "Default")
      (node (ref "U5") (pin "27") (pinfunction "OSCI_27") (pintype "passive+no_connect"))
    )
    (net (code "98") (name "unconnected-(U5-OSCO-Pad28)") (class "Default")
      (node (ref "U5") (pin "28") (pinfunction "OSCO_28") (pintype "passive+no_connect"))
    )
    (net (code "99") (name "unconnected-(U5-RESET-Pad19)") (class "Default")
      (node (ref "U5") (pin "19") (pinfunction "RESET_19") (pintype "passive+no_connect"))
    )
    (net (code "100") (name "unconnected-(U5-RI-Pad6)") (class "Default")
      (node (ref "U5") (pin "6") (pinfunction "RI_6") (pintype "passive+no_connect"))
    )
    (net (code "101") (name "unconnected-(U5-RTS-Pad3)") (class "Default")
      (node (ref "U5") (pin "3") (pinfunction "RTS_3") (pintype "passive+no_connect"))
    )
  )
)
